# 12-MSP430.net
KiCad netlist of a schematic drawn in Altium Designer
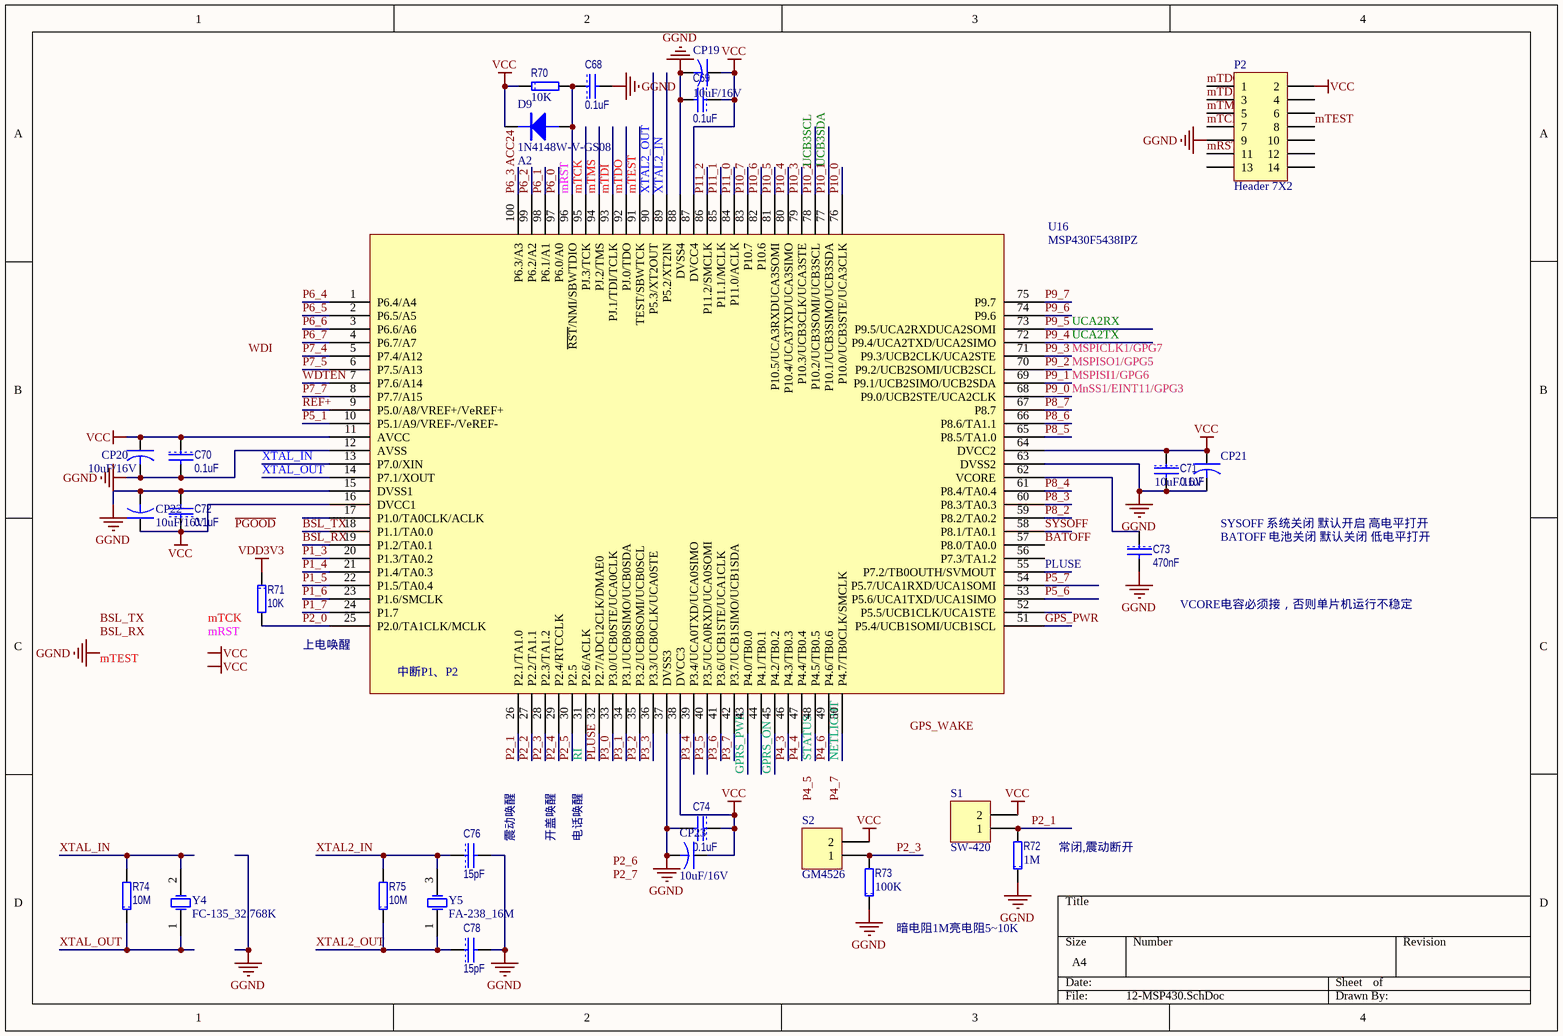
[diagram p0: 12-MSP430.SchDoc]

(export (version "E")
  (design (tool "Eeschema 10.0.6"))
  (components
    (comp (ref "C68")
      (value "0.1uF")
      (footprint "1608[0603]")
      (description "Capacitor")
      (fields (field (name "MANUFACTURER") "TDK"))
      (libsource (lib "*") (part "CAP"))
    )
    (comp (ref "C69")
      (value "0.1uF")
      (footprint "1608[0603]")
      (description "Capacitor")
      (fields (field (name "MANUFACTURER") "TDK"))
      (libsource (lib "*") (part "CAP"))
    )
    (comp (ref "C70")
      (value "0.1uF")
      (footprint "1608[0603]")
      (description "Capacitor")
      (fields (field (name "MANUFACTURER") "TDK"))
      (libsource (lib "*") (part "CAP"))
    )
    (comp (ref "C71")
      (value "0.1uF")
      (footprint "1608[0603]")
      (description "Capacitor")
      (fields (field (name "MANUFACTURER") "TDK"))
      (libsource (lib "*") (part "CAP"))
    )
    (comp (ref "C72")
      (value "0.1uF")
      (footprint "1608[0603]")
      (description "Capacitor")
      (fields (field (name "MANUFACTURER") "TDK"))
      (libsource (lib "*") (part "CAP"))
    )
    (comp (ref "C73")
      (value "470nF")
      (footprint "1608[0603]")
      (description "Capacitor")
      (fields (field (name "MANUFACTURER") "TDK"))
      (libsource (lib "*") (part "CAP"))
    )
    (comp (ref "C74")
      (value "0.1uF")
      (footprint "1608[0603]")
      (description "Capacitor")
      (fields (field (name "MANUFACTURER") "TDK"))
      (libsource (lib "*") (part "CAP"))
    )
    (comp (ref "C76")
      (value "15pF")
      (footprint "1608[0603]")
      (description "Capacitor")
      (fields (field (name "MANUFACTURER") "TDK"))
      (libsource (lib "*") (part "CAP"))
    )
    (comp (ref "C78")
      (value "15pF")
      (footprint "1608[0603]")
      (description "Capacitor")
      (fields (field (name "MANUFACTURER") "TDK"))
      (libsource (lib "*") (part "CAP"))
    )
    (comp (ref "CP19")
      (value "10uF/16V")
      (footprint "3216[1206]")
      (description "Tantalum Capacitor")
      (libsource (lib "*") (part "CAPACITOR"))
    )
    (comp (ref "CP20")
      (value "10uF/16V")
      (footprint "3216[1206]")
      (description "Tantalum Capacitor")
      (libsource (lib "*") (part "CAPACITOR"))
    )
    (comp (ref "CP21")
      (value "10uF/16V")
      (footprint "3216[1206]")
      (description "Tantalum Capacitor")
      (libsource (lib "*") (part "CAPACITOR"))
    )
    (comp (ref "CP22")
      (value "10uF/16V")
      (footprint "3216[1206]")
      (description "Tantalum Capacitor")
      (libsource (lib "*") (part "CAPACITOR"))
    )
    (comp (ref "CP23")
      (value "10uF/16V")
      (footprint "3216[1206]")
      (description "Tantalum Capacitor")
      (libsource (lib "*") (part "CAPACITOR"))
    )
    (comp (ref "D9")
      (value "1N4148W-V-GS08")
      (footprint "SOD323")
      (description "二极管 - 通用，功率，开关 100V Io/150mA")
      (fields (field (name "MANUFACTURER") "Vishay Semiconductors") (field (name "ALTIUM_VALUE") "A2"))
      (libsource (lib "IN4148") (part "1N4148W"))
    )
    (comp (ref "P2")
      (value "Header 7X2")
      (footprint "HDR2X7")
      (description "Header, 7-Pin, Dual row")
      (fields (field (name "PUBLISHER") "Altium Limited"))
      (libsource (lib "Miscellaneous Connectors") (part "Header 7X2"))
    )
    (comp (ref "R70")
      (value "10K")
      (footprint "1608[0603]R")
      (description "厚膜电阻器 - SMD 1/10watt 10Kohms 1%")
      (fields
        (field (name "MANUFACTURER") "Vishay / Dale")
        (field (name "MANUFACTURER PART NUMBER") "CRCW060310K0FKEA")
      )
      (libsource (lib "10K 1%") (part "RES"))
    )
    (comp (ref "R71")
      (value "10K")
      (footprint "1608[0603]R")
      (description "RES")
      (libsource (lib "*") (part "RES"))
    )
    (comp (ref "R72")
      (value "1M")
      (footprint "1608[0603]R")
      (description "厚膜电阻器 - SMD 1/10watt 1.0Mohms 1%")
      (fields
        (field (name "MANUFACTURER") "Vishay / Dale")
        (field (name "MANUFACTURER PART NUMBER") "CRCW06031M00FKEA")
      )
      (libsource (lib "1M 1%") (part "RES"))
    )
    (comp (ref "R73")
      (value "100K")
      (footprint "1608[0603]R")
      (description "厚膜电阻器 - SMD 1/10watt 100Kohms 1%")
      (fields
        (field (name "MANUFACTURER") "Vishay / Dale")
        (field (name "MANUFACTURER PART NUMBER") "CRCW0603100KFKEA")
      )
      (libsource (lib "100K 1%") (part "RES"))
    )
    (comp (ref "R74")
      (value "10M")
      (footprint "1608[0603]R")
      (description "RES")
      (libsource (lib "*") (part "RES"))
    )
    (comp (ref "R75")
      (value "10M")
      (footprint "1608[0603]R")
      (description "RES")
      (libsource (lib "*") (part "RES"))
    )
    (comp (ref "S1")
      (value "SW-420")
      (footprint "SW-420")
      (description "插针 工业级震动传感器")
      (fields (field (name "PUBLISHER") "Altium Limited"))
      (libsource (lib "Miscellaneous Connectors") (part "Header 2"))
    )
    (comp (ref "S2")
      (value "GM4526")
      (footprint "GM4526")
      (description "插针 光敏传感器")
      (fields (field (name "PUBLISHER") "Altium Limited"))
      (libsource (lib "Miscellaneous Connectors") (part "Header 2"))
    )
    (comp (ref "U16")
      (value "MSP430F5438IPZ")
      (footprint "TQFP100_N")
      (description "处理器")
      (libsource (lib "MSP430") (part "MSP430F5438"))
    )
    (comp (ref "Y4")
      (value "FC-135_32.768K")
      (footprint "FC-135")
      (description "Crystal Oscillator")
      (fields (field (name "PUBLISHER") "Altium Limited"))
      (libsource (lib "Miscellaneous Devices") (part "XTAL"))
    )
    (comp (ref "Y5")
      (value "FA-238_16M")
      (footprint "FA-238")
      (description "Crystal Oscillator")
      (fields (field (name "PUBLISHER") "Altium Limited"))
      (libsource (lib "") (part "XTAL_1"))
    )
  )
  (nets
    (net (code "1") (name "/ACC24") (class "Default")
      (node (ref "U16") (pin "100") (pinfunction "P6.3/A3_100") (pintype "passive"))
    )
    (net (code "2") (name "/BATOFF") (class "Default")
      (node (ref "U16") (pin "57") (pinfunction "P8.0/TA0.0_57") (pintype "passive"))
    )
    (net (code "3") (name "/BSL_RX") (class "Default")
      (node (ref "U16") (pin "19") (pinfunction "P1.2/TA0.1_19") (pintype "passive"))
    )
    (net (code "4") (name "/BSL_TX") (class "Default")
      (node (ref "U16") (pin "18") (pinfunction "P1.1/TA0.0_18") (pintype "passive"))
    )
    (net (code "5") (name "/GPRS_ON") (class "Default")
      (node (ref "U16") (pin "45") (pinfunction "P4.2/TB0.2_45") (pintype "passive"))
    )
    (net (code "6") (name "/GPRS_PWR") (class "Default")
      (node (ref "U16") (pin "43") (pinfunction "P4.0/TB0.0_43") (pintype "passive"))
    )
    (net (code "7") (name "/GPS_PWR") (class "Default")
      (node (ref "U16") (pin "51") (pinfunction "P5.4/UCB1SOMI/UCB1SCL_51") (pintype "passive"))
    )
    (net (code "9") (name "/MSPICLK1{slash}GPG7") (class "Default")
      (node (ref "U16") (pin "71") (pinfunction "P9.3/UCB2CLK/UCA2STE_71") (pintype "passive"))
    )
    (net (code "10") (name "/MSPISI1{slash}GPG6") (class "Default")
      (node (ref "U16") (pin "69") (pinfunction "P9.1/UCB2SIMO/UCB2SDA_69") (pintype "passive"))
    )
    (net (code "11") (name "/MSPISO1{slash}GPG5") (class "Default")
      (node (ref "U16") (pin "70") (pinfunction "P9.2/UCB2SOMI/UCB2SCL_70") (pintype "passive"))
    )
    (net (code "12") (name "/MnSS1{slash}EINT11{slash}GPG3") (class "Default")
      (node (ref "U16") (pin "68") (pinfunction "P9.0/UCB2STE/UCA2CLK_68") (pintype "passive"))
    )
    (net (code "13") (name "/NETLIGHT") (class "Default")
      (node (ref "U16") (pin "50") (pinfunction "P4.7/TB0CLK/SMCLK_50") (pintype "passive"))
    )
    (net (code "14") (name "/P1_3") (class "Default")
      (node (ref "U16") (pin "20") (pinfunction "P1.3/TA0.2_20") (pintype "passive"))
    )
    (net (code "15") (name "/P1_4") (class "Default")
      (node (ref "U16") (pin "21") (pinfunction "P1.4/TA0.3_21") (pintype "passive"))
    )
    (net (code "16") (name "/P1_5") (class "Default")
      (node (ref "U16") (pin "22") (pinfunction "P1.5/TA0.4_22") (pintype "passive"))
    )
    (net (code "17") (name "/P1_6") (class "Default")
      (node (ref "U16") (pin "23") (pinfunction "P1.6/SMCLK_23") (pintype "passive"))
    )
    (net (code "18") (name "/P1_7") (class "Default")
      (node (ref "U16") (pin "24") (pinfunction "P1.7_24") (pintype "passive"))
    )
    (net (code "19") (name "/P2_0") (class "Default")
      (node (ref "R71") (pin "2") (pinfunction "2_2") (pintype "passive"))
      (node (ref "U16") (pin "25") (pinfunction "P2.0/TA1CLK/MCLK_25") (pintype "passive"))
    )
    (net (code "20") (name "/P2_1") (class "Default")
      (node (ref "R72") (pin "2") (pinfunction "2_2") (pintype "passive"))
      (node (ref "S1") (pin "1") (pinfunction "1_1") (pintype "passive"))
      (node (ref "U16") (pin "26") (pinfunction "P2.1/TA1.0_26") (pintype "passive"))
    )
    (net (code "21") (name "/P2_2") (class "Default")
      (node (ref "U16") (pin "27") (pinfunction "P2.2/TA1.1_27") (pintype "passive"))
    )
    (net (code "22") (name "/P2_3") (class "Default")
      (node (ref "R73") (pin "2") (pinfunction "2_2") (pintype "passive"))
      (node (ref "S2") (pin "1") (pinfunction "1_1") (pintype "passive"))
      (node (ref "U16") (pin "28") (pinfunction "P2.3/TA1.2_28") (pintype "passive"))
    )
    (net (code "23") (name "/P2_4") (class "Default")
      (node (ref "U16") (pin "29") (pinfunction "P2.4/RTCCLK_29") (pintype "passive"))
    )
    (net (code "24") (name "/P2_5") (class "Default")
      (node (ref "U16") (pin "30") (pinfunction "P2.5_30") (pintype "passive"))
    )
    (net (code "27") (name "/P3_0") (class "Default")
      (node (ref "U16") (pin "33") (pinfunction "P3.0/UCB0STE/UCA0CLK_33") (pintype "passive"))
    )
    (net (code "28") (name "/P3_1") (class "Default")
      (node (ref "U16") (pin "34") (pinfunction "P3.1/UCB0SIMO/UCB0SDA_34") (pintype "passive"))
    )
    (net (code "29") (name "/P3_2") (class "Default")
      (node (ref "U16") (pin "35") (pinfunction "P3.2/UCB0SOMI/UCB0SCL_35") (pintype "passive"))
    )
    (net (code "30") (name "/P3_3") (class "Default")
      (node (ref "U16") (pin "36") (pinfunction "P3.3/UCB0CLK/UCA0STE_36") (pintype "passive"))
    )
    (net (code "31") (name "/P3_4") (class "Default")
      (node (ref "U16") (pin "39") (pinfunction "P3.4/UCA0TXD/UCA0SIMO_39") (pintype "passive"))
    )
    (net (code "32") (name "/P3_5") (class "Default")
      (node (ref "U16") (pin "40") (pinfunction "P3.5/UCA0RXD/UCA0SOMI_40") (pintype "passive"))
    )
    (net (code "33") (name "/P3_6") (class "Default")
      (node (ref "U16") (pin "41") (pinfunction "P3.6/UCB1STE/UCA1CLK_41") (pintype "passive"))
    )
    (net (code "34") (name "/P3_7") (class "Default")
      (node (ref "U16") (pin "42") (pinfunction "P3.7/UCB1SIMO/UCB1SDA_42") (pintype "passive"))
    )
    (net (code "35") (name "/P4_3") (class "Default")
      (node (ref "U16") (pin "46") (pinfunction "P4.3/TB0.3_46") (pintype "passive"))
    )
    (net (code "36") (name "/P4_4") (class "Default")
      (node (ref "U16") (pin "47") (pinfunction "P4.4/TB0.4_47") (pintype "passive"))
    )
    (net (code "38") (name "/P4_6") (class "Default")
      (node (ref "U16") (pin "49") (pinfunction "P4.6/TB0.6_49") (pintype "passive"))
    )
    (net (code "40") (name "/P5_1") (class "Default")
      (node (ref "U16") (pin "10") (pinfunction "P5.1/A9/VREF-/VeREF-_10") (pintype "passive"))
    )
    (net (code "41") (name "/P5_6") (class "Default")
      (node (ref "U16") (pin "53") (pinfunction "P5.6/UCA1TXD/UCA1SIMO_53") (pintype "passive"))
    )
    (net (code "42") (name "/P5_7") (class "Default")
      (node (ref "U16") (pin "54") (pinfunction "P5.7/UCA1RXD/UCA1SOMI_54") (pintype "passive"))
    )
    (net (code "43") (name "/P6_0") (class "Default")
      (node (ref "U16") (pin "97") (pinfunction "P6.0/A0_97") (pintype "passive"))
    )
    (net (code "44") (name "/P6_1") (class "Default")
      (node (ref "U16") (pin "98") (pinfunction "P6.1/A1_98") (pintype "passive"))
    )
    (net (code "45") (name "/P6_2") (class "Default")
      (node (ref "U16") (pin "99") (pinfunction "P6.2/A2_99") (pintype "passive"))
    )
    (net (code "46") (name "/P6_4") (class "Default")
      (node (ref "U16") (pin "1") (pinfunction "P6.4/A4_1") (pintype "passive"))
    )
    (net (code "47") (name "/P6_5") (class "Default")
      (node (ref "U16") (pin "2") (pinfunction "P6.5/A5_2") (pintype "passive"))
    )
    (net (code "48") (name "/P6_6") (class "Default")
      (node (ref "U16") (pin "3") (pinfunction "P6.6/A6_3") (pintype "passive"))
    )
    (net (code "49") (name "/P6_7") (class "Default")
      (node (ref "U16") (pin "4") (pinfunction "P6.7/A7_4") (pintype "passive"))
    )
    (net (code "50") (name "/P7_4") (class "Default")
      (node (ref "U16") (pin "5") (pinfunction "P7.4/A12_5") (pintype "passive"))
    )
    (net (code "51") (name "/P7_5") (class "Default")
      (node (ref "U16") (pin "6") (pinfunction "P7.5/A13_6") (pintype "passive"))
    )
    (net (code "52") (name "/P7_7") (class "Default")
      (node (ref "U16") (pin "8") (pinfunction "P7.7/A15_8") (pintype "passive"))
    )
    (net (code "53") (name "/P8_2") (class "Default")
      (node (ref "U16") (pin "59") (pinfunction "P8.2/TA0.2_59") (pintype "passive"))
    )
    (net (code "54") (name "/P8_3") (class "Default")
      (node (ref "U16") (pin "60") (pinfunction "P8.3/TA0.3_60") (pintype "passive"))
    )
    (net (code "55") (name "/P8_4") (class "Default")
      (node (ref "U16") (pin "61") (pinfunction "P8.4/TA0.4_61") (pintype "passive"))
    )
    (net (code "56") (name "/P8_5") (class "Default")
      (node (ref "U16") (pin "65") (pinfunction "P8.5/TA1.0_65") (pintype "passive"))
    )
    (net (code "57") (name "/P8_6") (class "Default")
      (node (ref "U16") (pin "66") (pinfunction "P8.6/TA1.1_66") (pintype "passive"))
    )
    (net (code "58") (name "/P8_7") (class "Default")
      (node (ref "U16") (pin "67") (pinfunction "P8.7_67") (pintype "passive"))
    )
    (net (code "59") (name "/P9_4") (class "Default")
      (node (ref "U16") (pin "72") (pinfunction "P9.4/UCA2TXD/UCA2SIMO_72") (pintype "passive"))
    )
    (net (code "60") (name "/P9_5") (class "Default")
      (node (ref "U16") (pin "73") (pinfunction "P9.5/UCA2RXDUCA2SOMI_73") (pintype "passive"))
    )
    (net (code "61") (name "/P9_6") (class "Default")
      (node (ref "U16") (pin "74") (pinfunction "P9.6_74") (pintype "passive"))
    )
    (net (code "62") (name "/P9_7") (class "Default")
      (node (ref "U16") (pin "75") (pinfunction "P9.7_75") (pintype "passive"))
    )
    (net (code "63") (name "/P10_0") (class "Default")
      (node (ref "U16") (pin "76") (pinfunction "P10.0/UCB3STE/UCA3CLK_76") (pintype "passive"))
    )
    (net (code "64") (name "/P10_1") (class "Default")
      (node (ref "U16") (pin "77") (pinfunction "P10.1/UCB3SIMO/UCB3SDA_77") (pintype "passive"))
    )
    (net (code "65") (name "/P10_2") (class "Default")
      (node (ref "U16") (pin "78") (pinfunction "P10.2/UCB3SOMI/UCB3SCL_78") (pintype "passive"))
    )
    (net (code "66") (name "/P10_3") (class "Default")
      (node (ref "U16") (pin "79") (pinfunction "P10.3/UCB3CLK/UCA3STE_79") (pintype "passive"))
    )
    (net (code "67") (name "/P10_4") (class "Default")
      (node (ref "U16") (pin "80") (pinfunction "P10.4/UCA3TXD/UCA3SIMO_80") (pintype "passive"))
    )
    (net (code "68") (name "/P10_5") (class "Default")
      (node (ref "U16") (pin "81") (pinfunction "P10.5/UCA3RXDUCA3SOMI_81") (pintype "passive"))
    )
    (net (code "69") (name "/P10_6") (class "Default")
      (node (ref "U16") (pin "82") (pinfunction "P10.6_82") (pintype "passive"))
    )
    (net (code "70") (name "/P10_7") (class "Default")
      (node (ref "U16") (pin "83") (pinfunction "P10.7_83") (pintype "passive"))
    )
    (net (code "71") (name "/P11_0") (class "Default")
      (node (ref "U16") (pin "84") (pinfunction "P11.0/ACLK_84") (pintype "passive"))
    )
    (net (code "72") (name "/P11_1") (class "Default")
      (node (ref "U16") (pin "85") (pinfunction "P11.1/MCLK_85") (pintype "passive"))
    )
    (net (code "73") (name "/P11_2") (class "Default")
      (node (ref "U16") (pin "86") (pinfunction "P11.2/SMCLK_86") (pintype "passive"))
    )
    (net (code "74") (name "/PLUSE") (class "Default")
      (node (ref "U16") (pin "32") (pinfunction "P2.7/ADC12CLK/DMAE0_32") (pintype "passive"))
      (node (ref "U16") (pin "55") (pinfunction "P7.2/TB0OUTH/SVMOUT_55") (pintype "passive"))
    )
    (net (code "75") (name "/REF+") (class "Default")
      (node (ref "U16") (pin "9") (pinfunction "P5.0/A8/VREF+/VeREF+_9") (pintype "passive"))
    )
    (net (code "76") (name "/RI") (class "Default")
      (node (ref "U16") (pin "31") (pinfunction "P2.6/ACLK_31") (pintype "passive"))
    )
    (net (code "77") (name "/STATUS") (class "Default")
      (node (ref "U16") (pin "48") (pinfunction "P4.5/TB0.5_48") (pintype "passive"))
    )
    (net (code "78") (name "/SYSOFF") (class "Default")
      (node (ref "U16") (pin "58") (pinfunction "P8.1/TA0.1_58") (pintype "passive"))
    )
    (net (code "80") (name "/WDTEN") (class "Default")
      (node (ref "U16") (pin "7") (pinfunction "P7.6/A14_7") (pintype "passive"))
    )
    (net (code "81") (name "/XTAL2_IN") (class "Default")
      (node (ref "C76") (pin "1") (pinfunction "1_1") (pintype "passive"))
      (node (ref "R75") (pin "2") (pinfunction "2_2") (pintype "passive"))
      (node (ref "U16") (pin "89") (pinfunction "P5.2/XT2IN_89") (pintype "passive"))
      (node (ref "Y5") (pin "3") (pinfunction "OSC2_3") (pintype "passive"))
    )
    (net (code "82") (name "/XTAL2_OUT") (class "Default")
      (node (ref "C78") (pin "1") (pinfunction "1_1") (pintype "passive"))
      (node (ref "R75") (pin "1") (pinfunction "1_1") (pintype "passive"))
      (node (ref "U16") (pin "90") (pinfunction "P5.3/XT2OUT_90") (pintype "passive"))
      (node (ref "Y5") (pin "1") (pinfunction "OSC1_1") (pintype "passive"))
    )
    (net (code "83") (name "/XTAL_IN") (class "Default")
      (node (ref "R74") (pin "2") (pinfunction "2_2") (pintype "passive"))
      (node (ref "U16") (pin "13") (pinfunction "P7.0/XIN_13") (pintype "passive"))
      (node (ref "Y4") (pin "2") (pinfunction "OSC2_2") (pintype "passive"))
    )
    (net (code "84") (name "/XTAL_OUT") (class "Default")
      (node (ref "R74") (pin "1") (pinfunction "1_1") (pintype "passive"))
      (node (ref "U16") (pin "14") (pinfunction "P7.1/XOUT_14") (pintype "passive"))
      (node (ref "Y4") (pin "1") (pinfunction "OSC1_1") (pintype "passive"))
    )
    (net (code "85") (name "/mRST") (class "Default")
      (node (ref "C68") (pin "1") (pinfunction "1_1") (pintype "passive"))
      (node (ref "D9") (pin "1") (pinfunction "A_1") (pintype "passive"))
      (node (ref "P2") (pin "11") (pinfunction "11_11") (pintype "passive"))
      (node (ref "R70") (pin "2") (pinfunction "2_2") (pintype "passive"))
      (node (ref "U16") (pin "96") (pinfunction "~{RST}/NMI/SBWTDIO_96") (pintype "passive"))
    )
    (net (code "86") (name "/mTCK") (class "Default")
      (node (ref "P2") (pin "7") (pinfunction "7_7") (pintype "passive"))
      (node (ref "U16") (pin "95") (pinfunction "PJ.3/TCK_95") (pintype "passive"))
    )
    (net (code "87") (name "/mTDI") (class "Default")
      (node (ref "P2") (pin "3") (pinfunction "3_3") (pintype "passive"))
      (node (ref "U16") (pin "93") (pinfunction "PJ.1/TDI/TCLK_93") (pintype "passive"))
    )
    (net (code "88") (name "/mTDO") (class "Default")
      (node (ref "P2") (pin "1") (pinfunction "1_1") (pintype "passive"))
      (node (ref "U16") (pin "92") (pinfunction "PJ.0/TDO_92") (pintype "passive"))
    )
    (net (code "89") (name "/mTEST") (class "Default")
      (node (ref "P2") (pin "8") (pinfunction "8_8") (pintype "passive"))
      (node (ref "U16") (pin "91") (pinfunction "TEST/SBWTCK_91") (pintype "passive"))
    )
    (net (code "90") (name "/mTMS") (class "Default")
      (node (ref "P2") (pin "5") (pinfunction "5_5") (pintype "passive"))
      (node (ref "U16") (pin "94") (pinfunction "PJ.2/TMS_94") (pintype "passive"))
    )
    (net (code "92") (name "GGND") (class "Default")
      (node (ref "C68") (pin "2") (pinfunction "2_2") (pintype "passive"))
      (node (ref "C69") (pin "2") (pinfunction "2_2") (pintype "passive"))
      (node (ref "C70") (pin "2") (pinfunction "2_2") (pintype "passive"))
      (node (ref "C71") (pin "2") (pinfunction "2_2") (pintype "passive"))
      (node (ref "C72") (pin "2") (pinfunction "2_2") (pintype "passive"))
      (node (ref "C73") (pin "2") (pinfunction "2_2") (pintype "passive"))
      (node (ref "C74") (pin "2") (pinfunction "2_2") (pintype "passive"))
      (node (ref "C76") (pin "2") (pinfunction "2_2") (pintype "passive"))
      (node (ref "C78") (pin "2") (pinfunction "2_2") (pintype "passive"))
      (node (ref "CP19") (pin "2") (pinfunction "2_2") (pintype "passive"))
      (node (ref "CP20") (pin "2") (pinfunction "2_2") (pintype "passive"))
      (node (ref "CP21") (pin "2") (pinfunction "2_2") (pintype "passive"))
      (node (ref "CP22") (pin "2") (pinfunction "2_2") (pintype "passive"))
      (node (ref "CP23") (pin "2") (pinfunction "2_2") (pintype "passive"))
      (node (ref "P2") (pin "9") (pinfunction "9_9") (pintype "passive"))
      (node (ref "R72") (pin "1") (pinfunction "1_1") (pintype "passive"))
      (node (ref "R73") (pin "1") (pinfunction "1_1") (pintype "passive"))
      (node (ref "U16") (pin "12") (pinfunction "AVSS_12") (pintype "passive"))
      (node (ref "U16") (pin "15") (pinfunction "DVSS1_15") (pintype "passive"))
      (node (ref "U16") (pin "37") (pinfunction "DVSS3_37") (pintype "passive"))
      (node (ref "U16") (pin "63") (pinfunction "DVSS2_63") (pintype "passive"))
      (node (ref "U16") (pin "88") (pinfunction "DVSS4_88") (pintype "passive"))
    )
    (net (code "93") (name "Net-(U16-VCORE)") (class "Default")
      (node (ref "C73") (pin "1") (pinfunction "1_1") (pintype "passive"))
      (node (ref "U16") (pin "62") (pinfunction "VCORE_62") (pintype "passive"))
    )
    (net (code "94") (name "VCC") (class "Default")
      (node (ref "C69") (pin "1") (pinfunction "1_1") (pintype "passive"))
      (node (ref "C70") (pin "1") (pinfunction "1_1") (pintype "passive"))
      (node (ref "C71") (pin "1") (pinfunction "1_1") (pintype "passive"))
      (node (ref "C72") (pin "1") (pinfunction "1_1") (pintype "passive"))
      (node (ref "C74") (pin "1") (pinfunction "1_1") (pintype "passive"))
      (node (ref "CP19") (pin "1") (pinfunction "1_1") (pintype "passive"))
      (node (ref "CP20") (pin "1") (pinfunction "1_1") (pintype "passive"))
      (node (ref "CP21") (pin "1") (pinfunction "1_1") (pintype "passive"))
      (node (ref "CP22") (pin "1") (pinfunction "1_1") (pintype "passive"))
      (node (ref "CP23") (pin "1") (pinfunction "1_1") (pintype "passive"))
      (node (ref "D9") (pin "2") (pinfunction "K_2") (pintype "passive"))
      (node (ref "P2") (pin "2") (pinfunction "2_2") (pintype "passive"))
      (node (ref "R70") (pin "1") (pinfunction "1_1") (pintype "passive"))
      (node (ref "S1") (pin "2") (pinfunction "2_2") (pintype "passive"))
      (node (ref "S2") (pin "2") (pinfunction "2_2") (pintype "passive"))
      (node (ref "U16") (pin "11") (pinfunction "AVCC_11") (pintype "passive"))
      (node (ref "U16") (pin "16") (pinfunction "DVCC1_16") (pintype "passive"))
      (node (ref "U16") (pin "38") (pinfunction "DVCC3_38") (pintype "passive"))
      (node (ref "U16") (pin "64") (pinfunction "DVCC2_64") (pintype "passive"))
      (node (ref "U16") (pin "87") (pinfunction "DVCC4_87") (pintype "passive"))
    )
    (net (code "95") (name "VDD3V3") (class "Default")
      (node (ref "R71") (pin "1") (pinfunction "1_1") (pintype "passive"))
    )
    (net (code "96") (name "unconnected-(P2-Pad4)") (class "Default")
      (node (ref "P2") (pin "4") (pinfunction "4_4") (pintype "passive"))
    )
    (net (code "97") (name "unconnected-(P2-Pad6)") (class "Default")
      (node (ref "P2") (pin "6") (pinfunction "6_6") (pintype "passive"))
    )
    (net (code "98") (name "unconnected-(P2-Pad10)") (class "Default")
      (node (ref "P2") (pin "10") (pinfunction "10_10") (pintype "passive"))
    )
    (net (code "99") (name "unconnected-(P2-Pad12)") (class "Default")
      (node (ref "P2") (pin "12") (pinfunction "12_12") (pintype "passive"))
    )
    (net (code "100") (name "unconnected-(P2-Pad13)") (class "Default")
      (node (ref "P2") (pin "13") (pinfunction "13_13") (pintype "passive"))
    )
    (net (code "101") (name "unconnected-(P2-Pad14)") (class "Default")
      (node (ref "P2") (pin "14") (pinfunction "14_14") (pintype "passive"))
    )
    (net (code "102") (name "unconnected-(U16-P1.0{slash}TA0CLK{slash}ACLK-Pad17)") (class "Default")
      (node (ref "U16") (pin "17") (pinfunction "P1.0/TA0CLK/ACLK_17") (pintype "passive"))
    )
    (net (code "103") (name "unconnected-(U16-P4.1{slash}TB0.1-Pad44)") (class "Default")
      (node (ref "U16") (pin "44") (pinfunction "P4.1/TB0.1_44") (pintype "passive"))
    )
    (net (code "104") (name "unconnected-(U16-P5.5{slash}UCB1CLK{slash}UCA1STE-Pad52)") (class "Default")
      (node (ref "U16") (pin "52") (pinfunction "P5.5/UCB1CLK/UCA1STE_52") (pintype "passive"))
    )
    (net (code "105") (name "unconnected-(U16-P7.3{slash}TA1.2-Pad56)") (class "Default")
      (node (ref "U16") (pin "56") (pinfunction "P7.3/TA1.2_56") (pintype "passive"))
    )
  )
)
